# SCK_DATA_BOARD_2_0_REV_05.net
KiCad netlist of a schematic drawn in EAGLE
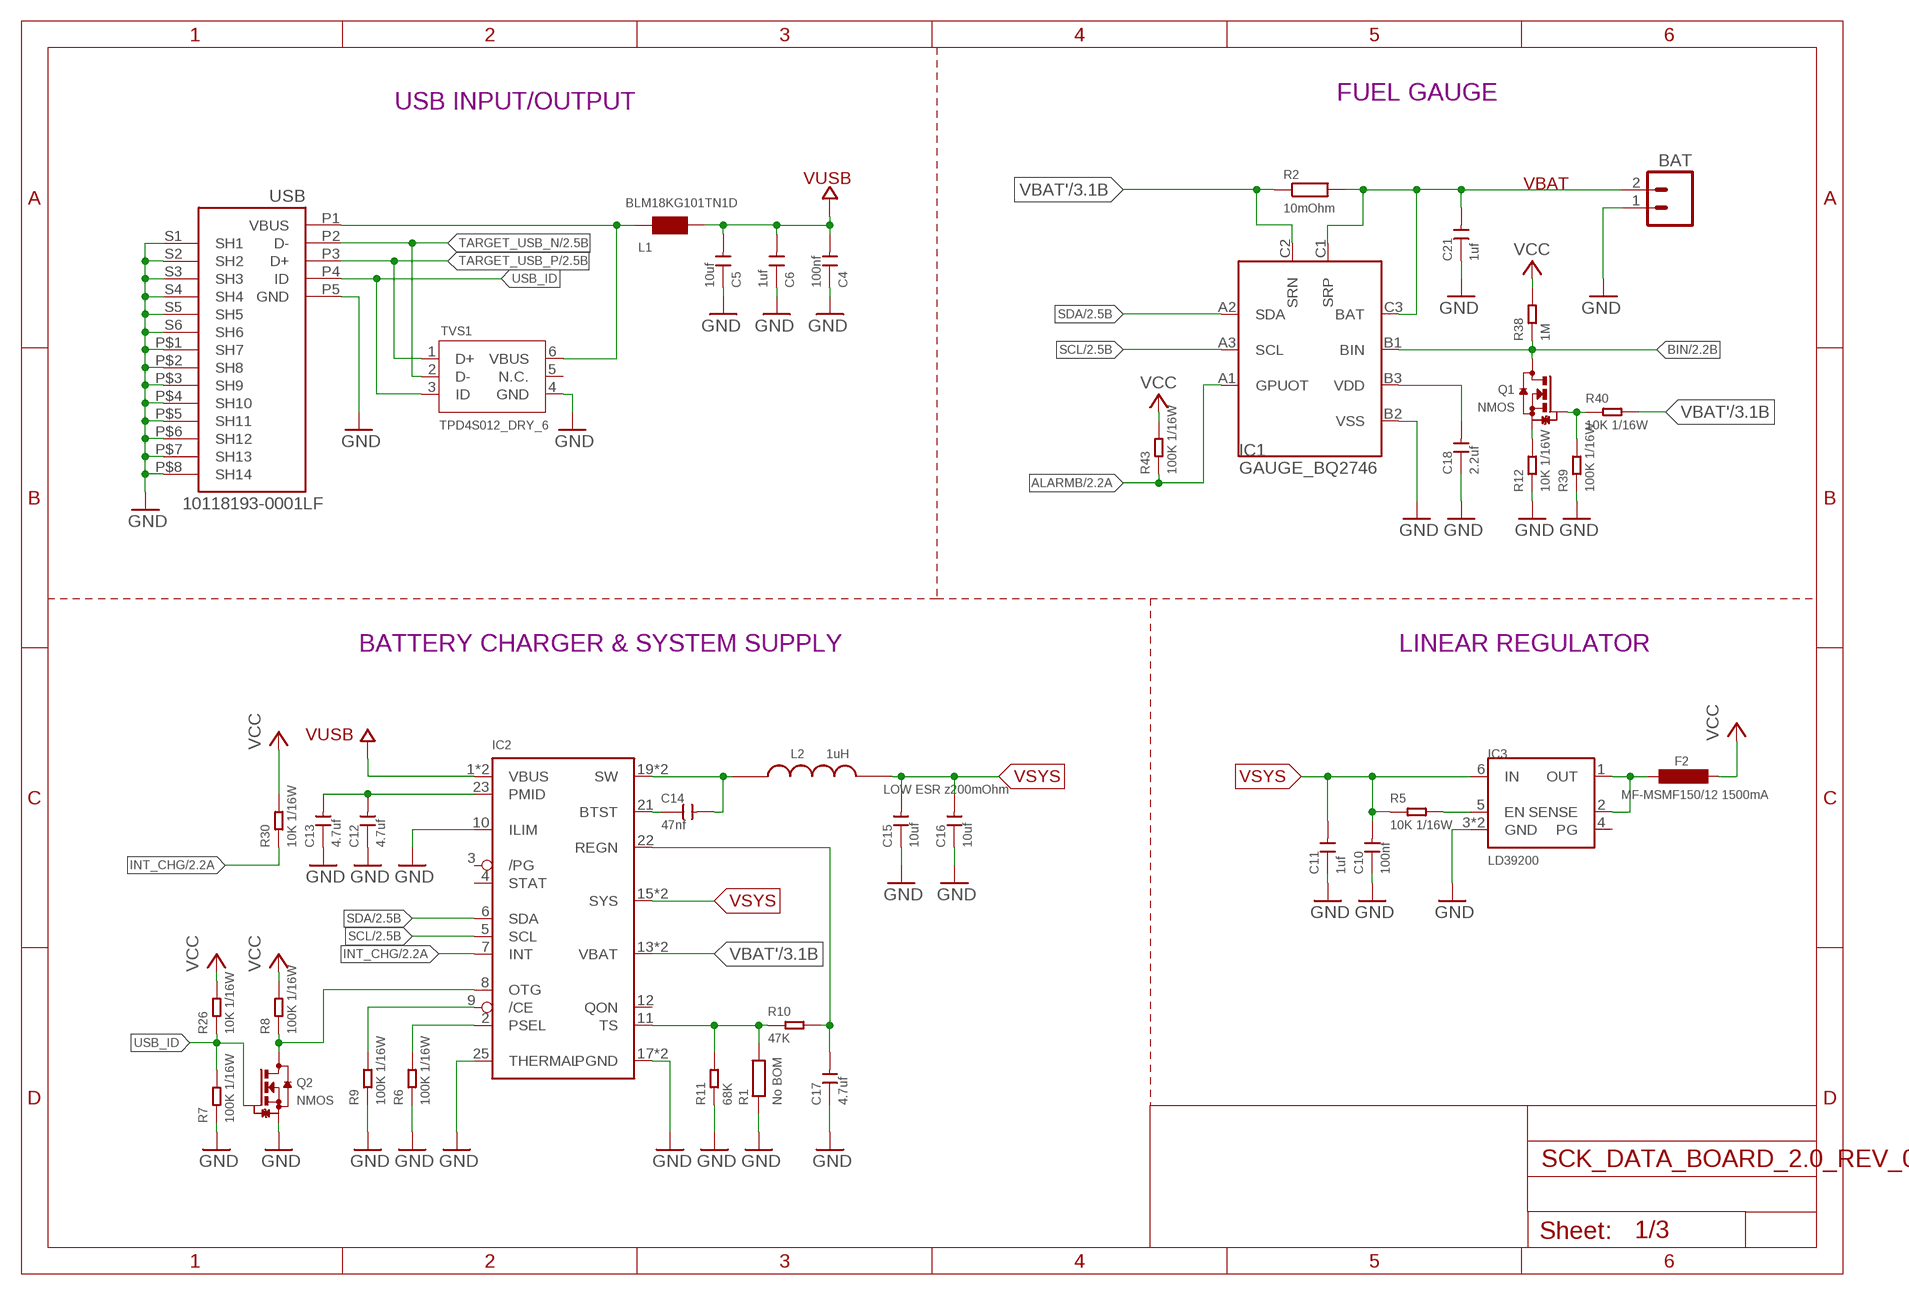
[diagram p0: schematic, sheet 1]
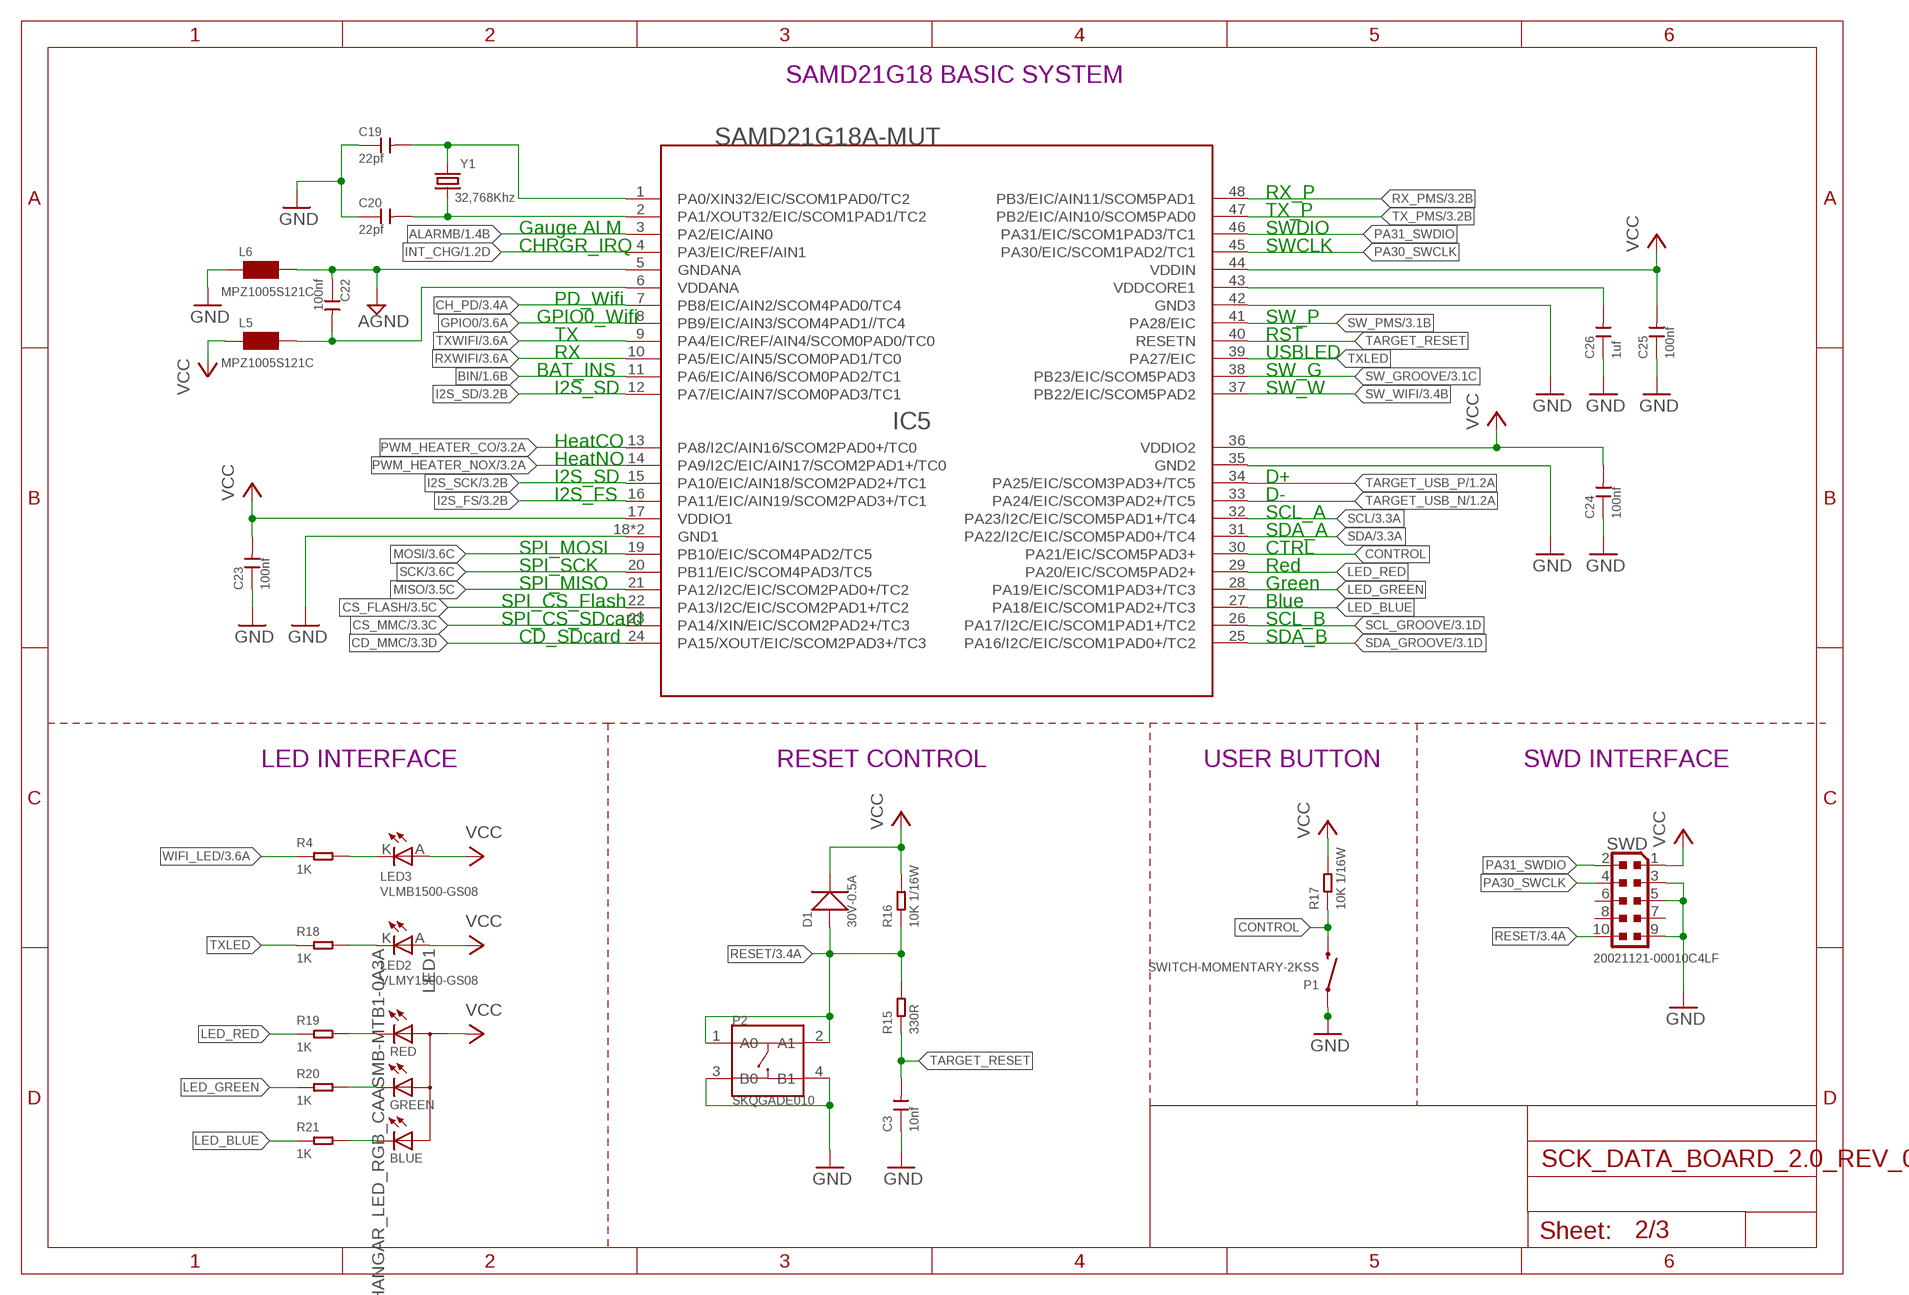
[diagram p1: schematic, sheet 2]
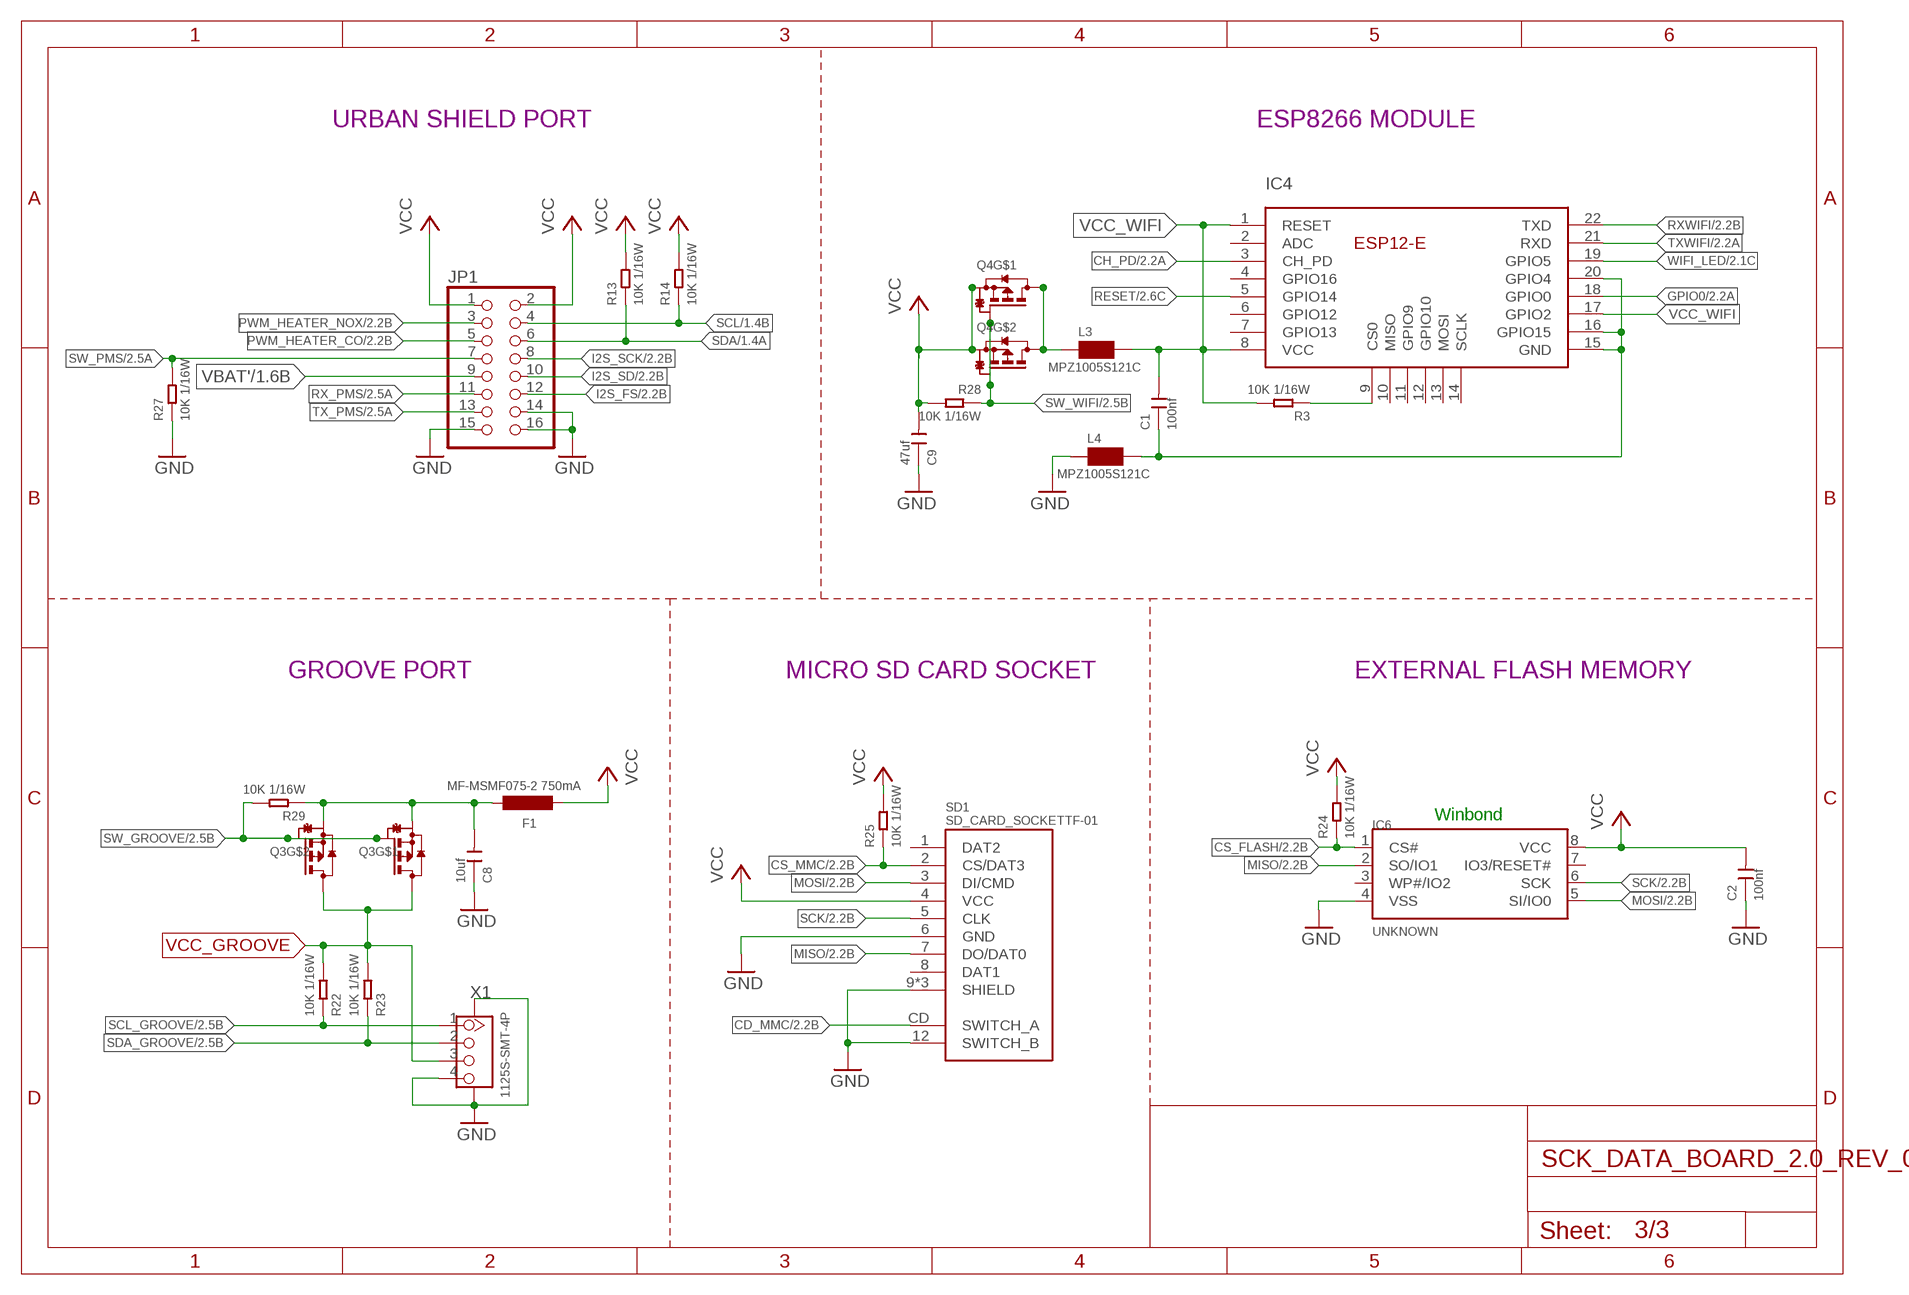
[diagram p2: schematic, sheet 3]

(export (version "E")
  (design (tool "Eeschema 10.0.6"))
  (components
    (comp (ref "BAT")
      (value "M02-JST-2MM-SMT")
      (footprint "eagle-import:S2B-PH")
      (libsource (lib "eagle-import") (part "M02-JST-2MM-SMT"))
    )
    (comp (ref "C4")
      (value "100nf")
      (footprint "eagle-import:C0805")
      (fields (field (name "MPN") "CC0805KRX7R9BB104"))
      (libsource (lib "eagle-import") (part "CERAMIC-100NF-50V-10%-X7R(0805)"))
    )
    (comp (ref "C5")
      (value "10uf")
      (footprint "eagle-import:C1206")
      (fields (field (name "MPN") "CC1206KKX5R8BB106"))
      (libsource (lib "eagle-import") (part "CERAMIC-10UF-25V-10%-X5R(1206)"))
    )
    (comp (ref "C6")
      (value "1uf")
      (footprint "eagle-import:C0805")
      (fields (field (name "MPN") "CC0805KKX7R8BB105"))
      (libsource (lib "eagle-import") (part "CERAMIC-1UF-25V-10%-X7R(0805)"))
    )
    (comp (ref "C10")
      (value "100nf")
      (footprint "eagle-import:C0603")
      (fields (field (name "MPN") "CC0603KRX7R9BB104"))
      (libsource (lib "eagle-import") (part "CERAMIC-100NF-50V-10%-X7R(0603)"))
    )
    (comp (ref "C11")
      (value "1uf")
      (footprint "eagle-import:C0805")
      (fields (field (name "MPN") "CC0805KKX7R8BB105"))
      (libsource (lib "eagle-import") (part "CERAMIC-1UF-25V-10%-X7R(0805)"))
    )
    (comp (ref "C12")
      (value "4.7uf")
      (footprint "eagle-import:C0603")
      (fields (field (name "MPN") "CC0603KRX5R6BB475"))
      (libsource (lib "eagle-import") (part "CERAMIC-4.7UF-10V-10%-X5R(0603)"))
    )
    (comp (ref "C13")
      (value "4.7uf")
      (footprint "eagle-import:C0603")
      (fields (field (name "MPN") "CC0603KRX5R6BB475"))
      (libsource (lib "eagle-import") (part "CERAMIC-4.7UF-10V-10%-X5R(0603)"))
    )
    (comp (ref "C14")
      (value "47nf")
      (footprint "eagle-import:C0402")
      (fields (field (name "MPN") "CC0402KRX7R8BB473"))
      (libsource (lib "eagle-import") (part "CERAMIC-47NF-25V-10%-X7R(0402)"))
    )
    (comp (ref "C15")
      (value "10uf")
      (footprint "eagle-import:C0603")
      (fields (field (name "MPN") "CC0603KRX5R6BB106"))
      (libsource (lib "eagle-import") (part "CERAMIC-10UF-10V-10%-X5R(0603)"))
    )
    (comp (ref "C16")
      (value "10uf")
      (footprint "eagle-import:C0603")
      (fields (field (name "MPN") "CC0603KRX5R6BB106"))
      (libsource (lib "eagle-import") (part "CERAMIC-10UF-10V-10%-X5R(0603)"))
    )
    (comp (ref "C17")
      (value "4.7uf")
      (footprint "eagle-import:C0805")
      (fields (field (name "MPN") "CC0805KKX5R8BB475"))
      (libsource (lib "eagle-import") (part "CERAMIC-4.7UF-25V-10%-X5R(0805)"))
    )
    (comp (ref "C18")
      (value "2.2uf")
      (footprint "eagle-import:C0603")
      (fields (field (name "MPN") "CC0603KRX7R6BB225"))
      (libsource (lib "eagle-import") (part "CERAMIC-2.2UF-10V-10%-X7R(0603)"))
    )
    (comp (ref "C21")
      (value "1uf")
      (footprint "eagle-import:C0805")
      (fields (field (name "MPN") "CC0805KKX7R8BB105"))
      (libsource (lib "eagle-import") (part "CERAMIC-1UF-25V-10%-X7R(0805)"))
    )
    (comp (ref "F2")
      (value "MF-MSMF150/12 1500mA")
      (footprint "eagle-import:L1812")
      (libsource (lib "eagle-import") (part "L-EUL1812"))
    )
    (comp (ref "IC1")
      (value "GAUGE_BQ2746")
      (footprint "eagle-import:BGA-9")
      (libsource (lib "eagle-import") (part "GAUGE_BQ2746"))
    )
    (comp (ref "IC2")
      (value "BQ24259_VQFN(24)")
      (footprint "eagle-import:24-PIN_VQFN_THPAD")
      (libsource (lib "eagle-import") (part "BQ24259_VQFN(24)"))
    )
    (comp (ref "IC3")
      (value "LD39200")
      (footprint "eagle-import:DFN6_3X3MM")
      (libsource (lib "eagle-import") (part "LD39200"))
    )
    (comp (ref "L1")
      (value "BLM18KG101TN1D")
      (footprint "eagle-import:WUERTH-ELEKTRONIK_0603")
      (libsource (lib "eagle-import") (part "WUERTH-ELEKTRONIK_WE-CBF_0603"))
    )
    (comp (ref "L2")
      (value "1uH")
      (footprint "eagle-import:HANGAR_C1210")
      (libsource (lib "eagle-import") (part "LQH32PN1R0NNCL"))
    )
    (comp (ref "Q1")
      (value "NMOS")
      (footprint "eagle-import:NMOS_UMT3")
      (libsource (lib "eagle-import") (part "NMOS_RJU003N03FRAT106"))
    )
    (comp (ref "Q2")
      (value "NMOS")
      (footprint "eagle-import:NMOS_UMT3")
      (libsource (lib "eagle-import") (part "NMOS_RJU003N03FRAT106"))
    )
    (comp (ref "R1")
      (value "No BOM")
      (footprint "eagle-import:HANGAR_R0402")
      (libsource (lib "eagle-import") (part "HANGAR_R-EU_R0402"))
    )
    (comp (ref "R2")
      (value "10mOhm")
      (footprint "eagle-import:HANGAR_R0603")
      (libsource (lib "eagle-import") (part "SCK_URBAN_SHIELD_v1.6_HANGAR_R-EU_R0603"))
    )
    (comp (ref "R5")
      (value "10K 1/16W")
      (footprint "eagle-import:R0402")
      (fields (field (name "MPN") "RC0402FR-0710KL"))
      (libsource (lib "eagle-import") (part "SMD-RES-10K-1%-1/16W(0402)"))
    )
    (comp (ref "R6")
      (value "100K 1/16W")
      (footprint "eagle-import:R0402")
      (fields (field (name "MPN") "RC0402JR-07100KL"))
      (libsource (lib "eagle-import") (part "SMD-RES-100K-5%-1/16W(0402)"))
    )
    (comp (ref "R7")
      (value "100K 1/16W")
      (footprint "eagle-import:R0402")
      (fields (field (name "MPN") "RC0402JR-07100KL"))
      (libsource (lib "eagle-import") (part "SMD-RES-100K-5%-1/16W(0402)"))
    )
    (comp (ref "R8")
      (value "100K 1/16W")
      (footprint "eagle-import:R0402")
      (fields (field (name "MPN") "RC0402JR-07100KL"))
      (libsource (lib "eagle-import") (part "SMD-RES-100K-5%-1/16W(0402)"))
    )
    (comp (ref "R9")
      (value "100K 1/16W")
      (footprint "eagle-import:R0402")
      (fields (field (name "MPN") "RC0402JR-07100KL"))
      (libsource (lib "eagle-import") (part "SMD-RES-100K-5%-1/16W(0402)"))
    )
    (comp (ref "R10")
      (value "47K")
      (footprint "eagle-import:R0402")
      (fields (field (name "MPN") "RC0402JR-0747KL"))
      (libsource (lib "eagle-import") (part "SMD-RES-47K-5%-1/16W(0402)"))
    )
    (comp (ref "R11")
      (value "68K")
      (footprint "eagle-import:R0402")
      (fields (field (name "MPN") "RC0402JR-0768KL"))
      (libsource (lib "eagle-import") (part "SMD-RES-68K-50V-5%(0402)"))
    )
    (comp (ref "R12")
      (value "10K 1/16W")
      (footprint "eagle-import:R0402")
      (fields (field (name "MPN") "RC0402FR-0710KL"))
      (libsource (lib "eagle-import") (part "SMD-RES-10K-1%-1/16W(0402)"))
    )
    (comp (ref "R26")
      (value "10K 1/16W")
      (footprint "eagle-import:R0402")
      (fields (field (name "MPN") "RC0402FR-0710KL"))
      (libsource (lib "eagle-import") (part "SMD-RES-10K-1%-1/16W(0402)"))
    )
    (comp (ref "R30")
      (value "10K 1/16W")
      (footprint "eagle-import:R0402")
      (fields (field (name "MPN") "RC0402FR-0710KL"))
      (libsource (lib "eagle-import") (part "SMD-RES-10K-1%-1/16W(0402)"))
    )
    (comp (ref "R38")
      (value "1M")
      (footprint "eagle-import:R0402")
      (fields (field (name "MPN") "RC0402JR-071ML"))
      (libsource (lib "eagle-import") (part "SMD-RES-1M-5%-1/16W(0402)"))
    )
    (comp (ref "R39")
      (value "100K 1/16W")
      (footprint "eagle-import:R0402")
      (fields (field (name "MPN") "RC0402JR-07100KL"))
      (libsource (lib "eagle-import") (part "Seeed-Resistor_SMD-RES-100K-5%-1/16W(0402)"))
    )
    (comp (ref "R40")
      (value "10K 1/16W")
      (footprint "eagle-import:R0402")
      (fields (field (name "MPN") "RC0402FR-0710KL"))
      (libsource (lib "eagle-import") (part "SMD-RES-10K-1%-1/16W(0402)"))
    )
    (comp (ref "R43")
      (value "100K 1/16W")
      (footprint "eagle-import:R0402")
      (fields (field (name "MPN") "RC0402JR-07100KL"))
      (libsource (lib "eagle-import") (part "Seeed-Resistor_SMD-RES-100K-5%-1/16W(0402)"))
    )
    (comp (ref "TVS1")
      (value "TPD4S012_DRY_6")
      (footprint "eagle-import:DRY6")
      (libsource (lib "eagle-import") (part "TPD4S012_DRY_6"))
    )
    (comp (ref "USB")
      (value "10118193-0001LF")
      (footprint "eagle-import:HANGAR_CON2_USB_MICRO_B_AT")
      (libsource (lib "eagle-import") (part "HANGAR_MYCON2_USB-MINI-B"))
    )
    (comp (ref "C3")
      (value "10nf")
      (footprint "eagle-import:C0402")
      (fields (field (name "MPN") "CC0402KRX7R9BB103"))
      (libsource (lib "eagle-import") (part "CERAMIC-10NF-50V-10%-X7R(0402)"))
    )
    (comp (ref "C19")
      (value "22pf")
      (footprint "eagle-import:C0402")
      (fields (field (name "MPN") "CC0402JRNPO9BN220"))
      (libsource (lib "eagle-import") (part "CERAMIC-22PF-50V-5%-NPO(0402)"))
    )
    (comp (ref "C20")
      (value "22pf")
      (footprint "eagle-import:C0402")
      (fields (field (name "MPN") "CC0402JRNPO9BN220"))
      (libsource (lib "eagle-import") (part "CERAMIC-22PF-50V-5%-NPO(0402)"))
    )
    (comp (ref "C22")
      (value "100nf")
      (footprint "eagle-import:C0402")
      (fields (field (name "MPN") "CC0402KRX7R8BB104"))
      (libsource (lib "eagle-import") (part "CERAMIC-100NF-25V-10%-X7R(0402)"))
    )
    (comp (ref "C23")
      (value "100nf")
      (footprint "eagle-import:C0402")
      (fields (field (name "MPN") "CC0402KRX7R8BB104"))
      (libsource (lib "eagle-import") (part "CERAMIC-100NF-25V-10%-X7R(0402)"))
    )
    (comp (ref "C24")
      (value "100nf")
      (footprint "eagle-import:C0402")
      (fields (field (name "MPN") "CC0402KRX7R8BB104"))
      (libsource (lib "eagle-import") (part "CERAMIC-100NF-25V-10%-X7R(0402)"))
    )
    (comp (ref "C25")
      (value "100nf")
      (footprint "eagle-import:C0402")
      (fields (field (name "MPN") "CC0402KRX7R8BB104"))
      (libsource (lib "eagle-import") (part "CERAMIC-100NF-25V-10%-X7R(0402)"))
    )
    (comp (ref "C26")
      (value "1uf")
      (footprint "eagle-import:C0402")
      (fields (field (name "MPN") "CC0402KRX5R6BB105"))
      (libsource (lib "eagle-import") (part "CERAMIC-1UF-10V-10%-X5R(0402)"))
    )
    (comp (ref "D1")
      (value "30V-0.5A")
      (footprint "eagle-import:SOD-323")
      (fields (field (name "MPN") "LRB551V-30T1G"))
      (libsource (lib "eagle-import") (part "SMD-DIODE-SCHOTTKY-30V-0.5A(SOD-323)"))
    )
    (comp (ref "IC5")
      (value "SAMD21G18A-MUT")
      (footprint "eagle-import:HANGAR_QFN48-7X7")
      (libsource (lib "eagle-import") (part "HANGAR_SAMD21G18A-MUT"))
    )
    (comp (ref "L5")
      (value "MPZ1005S121C")
      (footprint "eagle-import:0402")
      (libsource (lib "eagle-import") (part "WE-CBF_0402"))
    )
    (comp (ref "L6")
      (value "MPZ1005S121C")
      (footprint "eagle-import:0402")
      (libsource (lib "eagle-import") (part "WE-CBF_0402"))
    )
    (comp (ref "LED1")
      (value "HANGAR_LED_RGB_CAASMB-MTB1-0A3A")
      (footprint "eagle-import:HANGAR_P-LCC-4")
      (libsource (lib "eagle-import") (part "HANGAR_LED_RGB_CAASMB-MTB1-0A3A"))
    )
    (comp (ref "LED2")
      (value "VLMY1500-GS08")
      (footprint "eagle-import:DIODE_0402_R")
      (libsource (lib "eagle-import") (part "LED_SMALL"))
    )
    (comp (ref "LED3")
      (value "VLMB1500-GS08")
      (footprint "eagle-import:DIODE_0402_R")
      (libsource (lib "eagle-import") (part "LED_SMALL"))
    )
    (comp (ref "P1")
      (value "SWITCH-MOMENTARY-2KSS")
      (footprint "eagle-import:KSS241G")
      (libsource (lib "eagle-import") (part "SWITCH-MOMENTARY-2KSS"))
    )
    (comp (ref "P2")
      (value "SKQGADE010")
      (footprint "eagle-import:SW4-SMD-5.2X5.2X1.5MM")
      (libsource (lib "eagle-import") (part "SMD-BUTTON(4P-5.2X5.2X1.5MM-SKQGADE010)-SKQGADE010"))
    )
    (comp (ref "R4")
      (value "1K")
      (footprint "eagle-import:R0402")
      (fields (field (name "MPN") "RC0402JR-071KL"))
      (libsource (lib "eagle-import") (part "SMD-RES-1K-5%-1/16W(0402)"))
    )
    (comp (ref "R15")
      (value "330R")
      (footprint "eagle-import:R0402")
      (fields (field (name "MPN") "RC0402FR-07330RL"))
      (libsource (lib "eagle-import") (part "SMD-RES-330R-1%-1/16W(0402)"))
    )
    (comp (ref "R16")
      (value "10K 1/16W")
      (footprint "eagle-import:R0402")
      (fields (field (name "MPN") "RC0402FR-0710KL"))
      (libsource (lib "eagle-import") (part "SMD-RES-10K-1%-1/16W(0402)"))
    )
    (comp (ref "R17")
      (value "10K 1/16W")
      (footprint "eagle-import:R0402")
      (fields (field (name "MPN") "RC0402FR-0710KL"))
      (libsource (lib "eagle-import") (part "SMD-RES-10K-1%-1/16W(0402)"))
    )
    (comp (ref "R18")
      (value "1K")
      (footprint "eagle-import:R0402")
      (fields (field (name "MPN") "RC0402JR-071KL"))
      (libsource (lib "eagle-import") (part "SMD-RES-1K-5%-1/16W(0402)"))
    )
    (comp (ref "R19")
      (value "1K")
      (footprint "eagle-import:R0402")
      (fields (field (name "MPN") "RC0402JR-071KL"))
      (libsource (lib "eagle-import") (part "SMD-RES-1K-5%-1/16W(0402)"))
    )
    (comp (ref "R20")
      (value "1K")
      (footprint "eagle-import:R0402")
      (fields (field (name "MPN") "RC0402JR-071KL"))
      (libsource (lib "eagle-import") (part "SMD-RES-1K-5%-1/16W(0402)"))
    )
    (comp (ref "R21")
      (value "1K")
      (footprint "eagle-import:R0402")
      (fields (field (name "MPN") "RC0402JR-071KL"))
      (libsource (lib "eagle-import") (part "SMD-RES-1K-5%-1/16W(0402)"))
    )
    (comp (ref "SWD")
      (value "20021121-00010C4LF")
      (footprint "eagle-import:2X05_SMD_1.27MM")
      (libsource (lib "eagle-import") (part "PINHEAD_PINHD-2X5SMD"))
    )
    (comp (ref "Y1")
      (value "32,768Khz")
      (footprint "eagle-import:RESONATOR_EPSON_FC_145")
      (fields (field (name "PART_NUMBER") "ABS07-32.768KHZ-T"))
      (libsource (lib "eagle-import") (part "0213_ABS07-32.768KHZ-T"))
    )
    (comp (ref "C1")
      (value "100nf")
      (footprint "eagle-import:C0402")
      (fields (field (name "MPN") "CC0402KRX7R8BB104"))
      (libsource (lib "eagle-import") (part "CERAMIC-100NF-25V-10%-X7R(0402)"))
    )
    (comp (ref "C2")
      (value "100nf")
      (footprint "eagle-import:C0402")
      (fields (field (name "MPN") "CC0402KRX7R8BB104"))
      (libsource (lib "eagle-import") (part "CERAMIC-100NF-25V-10%-X7R(0402)"))
    )
    (comp (ref "C8")
      (value "10uf")
      (footprint "eagle-import:C1206")
      (fields (field (name "MPN") "CC1206KKX5R8BB106"))
      (libsource (lib "eagle-import") (part "CERAMIC-10UF-25V-10%-X5R(1206)"))
    )
    (comp (ref "C9")
      (value "47uf")
      (footprint "eagle-import:C1210")
      (fields (field (name "MPN") "GRM32ER71A476ME15L"))
      (libsource (lib "eagle-import") (part "CERAMIC-47UF-10V-20%-X7R(1210)"))
    )
    (comp (ref "F1")
      (value "MF-MSMF075-2 750mA")
      (footprint "eagle-import:L1812")
      (libsource (lib "eagle-import") (part "L-EUL1812"))
    )
    (comp (ref "IC4")
      (value "HANGAR_ESP-12-E")
      (footprint "eagle-import:HANGAR_ESP12-E")
      (libsource (lib "eagle-import") (part "HANGAR_ESP-12-E"))
    )
    (comp (ref "IC6")
      (value "UNKNOWN")
      (footprint "eagle-import:SOIC_8-208MILS")
      (libsource (lib "eagle-import") (part "FLASH_S25FL064L"))
    )
    (comp (ref "JP1")
      (value "PINHD_2X8FEM_SMD")
      (footprint "eagle-import:PINHD_2X8_SMD_FEMALE_UNHOLED")
      (libsource (lib "eagle-import") (part "PINHD_2X8FEM_SMD"))
    )
    (comp (ref "L3")
      (value "MPZ1005S121C")
      (footprint "eagle-import:0402")
      (libsource (lib "eagle-import") (part "WE-CBF_0402"))
    )
    (comp (ref "L4")
      (value "MPZ1005S121C")
      (footprint "eagle-import:0402")
      (libsource (lib "eagle-import") (part "WE-CBF_0402"))
    )
    (comp (ref "Q3")
      (value "PMOS")
      (footprint "eagle-import:HANGAR_POWERPAKSC70-6L")
      (libsource (lib "eagle-import") (part "MOSFETP_BOTH"))
    )
    (comp (ref "Q4")
      (value "PMOS")
      (footprint "eagle-import:HANGAR_POWERPAKSC70-6L")
      (libsource (lib "eagle-import") (part "MOSFETP_BOTH"))
    )
    (comp (ref "R3")
      (value "10K 1/16W")
      (footprint "eagle-import:R0402")
      (fields (field (name "MPN") "RC0402FR-0710KL"))
      (libsource (lib "eagle-import") (part "SMD-RES-10K-1%-1/16W(0402)"))
    )
    (comp (ref "R13")
      (value "10K 1/16W")
      (footprint "eagle-import:R0402")
      (fields (field (name "MPN") "RC0402FR-0710KL"))
      (libsource (lib "eagle-import") (part "SMD-RES-10K-1%-1/16W(0402)"))
    )
    (comp (ref "R14")
      (value "10K 1/16W")
      (footprint "eagle-import:R0402")
      (fields (field (name "MPN") "RC0402FR-0710KL"))
      (libsource (lib "eagle-import") (part "SMD-RES-10K-1%-1/16W(0402)"))
    )
    (comp (ref "R22")
      (value "10K 1/16W")
      (footprint "eagle-import:R0402")
      (fields (field (name "MPN") "RC0402FR-0710KL"))
      (libsource (lib "eagle-import") (part "SMD-RES-10K-1%-1/16W(0402)"))
    )
    (comp (ref "R23")
      (value "10K 1/16W")
      (footprint "eagle-import:R0402")
      (fields (field (name "MPN") "RC0402FR-0710KL"))
      (libsource (lib "eagle-import") (part "SMD-RES-10K-1%-1/16W(0402)"))
    )
    (comp (ref "R24")
      (value "10K 1/16W")
      (footprint "eagle-import:R0402")
      (fields (field (name "MPN") "RC0402FR-0710KL"))
      (libsource (lib "eagle-import") (part "SMD-RES-10K-1%-1/16W(0402)"))
    )
    (comp (ref "R25")
      (value "10K 1/16W")
      (footprint "eagle-import:R0402")
      (fields (field (name "MPN") "RC0402FR-0710KL"))
      (libsource (lib "eagle-import") (part "SMD-RES-10K-1%-1/16W(0402)"))
    )
    (comp (ref "R27")
      (value "10K 1/16W")
      (footprint "eagle-import:R0402")
      (fields (field (name "MPN") "RC0402FR-0710KL"))
      (libsource (lib "eagle-import") (part "Seeed-Resistor_SMD-RES-10K-1%-1/16W(0402)"))
    )
    (comp (ref "R28")
      (value "10K 1/16W")
      (footprint "eagle-import:R0402")
      (fields (field (name "MPN") "RC0402FR-0710KL"))
      (libsource (lib "eagle-import") (part "Seeed-Resistor_SMD-RES-10K-1%-1/16W(0402)"))
    )
    (comp (ref "R29")
      (value "10K 1/16W")
      (footprint "eagle-import:R0402")
      (fields (field (name "MPN") "RC0402FR-0710KL"))
      (libsource (lib "eagle-import") (part "Seeed-Resistor_SMD-RES-10K-1%-1/16W(0402)"))
    )
    (comp (ref "SD1")
      (value "SD_CARD_SOCKETTF-01")
      (footprint "eagle-import:TF-01")
      (libsource (lib "eagle-import") (part "SD_CARD_SOCKETTF-01"))
    )
    (comp (ref "X1")
      (value "1125S-SMT-4P")
      (footprint "eagle-import:HW4-SMD-2.0")
      (libsource (lib "eagle-import") (part "GROVE-CONNECTOR-SMD'DD'"))
    )
  )
  (nets
    (net (code "1") (name "AGND") (class "Default")
      (node (ref "C22") (pin "1") (pinfunction "1_1") (pintype "passive"))
      (node (ref "IC5") (pin "5") (pinfunction "GNDANA_5") (pintype "power_in"))
      (node (ref "L6") (pin "2") (pinfunction "2_2") (pintype "passive"))
    )
    (net (code "2") (name "ALARMB") (class "Default")
      (node (ref "IC1") (pin "A1") (pinfunction "GPUOT_A1") (pintype "bidirectional"))
      (node (ref "IC5") (pin "3") (pinfunction "PA2/EIC/AIN0_3") (pintype "bidirectional"))
      (node (ref "R43") (pin "1") (pinfunction "1_1") (pintype "passive"))
    )
    (net (code "3") (name "BIN") (class "Default")
      (node (ref "IC1") (pin "B1") (pinfunction "BIN_B1") (pintype "bidirectional"))
      (node (ref "IC5") (pin "11") (pinfunction "PA6/EIC/AIN6/SCOM0PAD2/TC1_11") (pintype "bidirectional"))
      (node (ref "Q1") (pin "3") (pinfunction "D_3") (pintype "passive"))
      (node (ref "R38") (pin "1") (pinfunction "1_1") (pintype "passive"))
    )
    (net (code "4") (name "CD_MMC") (class "Default")
      (node (ref "IC5") (pin "24") (pinfunction "PA15/XOUT/EIC/SCOM2PAD3+/TC3_24") (pintype "bidirectional"))
      (node (ref "SD1") (pin "CD") (pinfunction "SWITCH_A_CD") (pintype "bidirectional"))
    )
    (net (code "5") (name "CH_PD") (class "Default")
      (node (ref "IC4") (pin "3") (pinfunction "CH_PD_3") (pintype "input"))
      (node (ref "IC5") (pin "7") (pinfunction "PB8/EIC/AIN2/SCOM4PAD0/TC4_7") (pintype "bidirectional"))
    )
    (net (code "6") (name "CONTROL") (class "Default")
      (node (ref "IC5") (pin "30") (pinfunction "PA21/EIC/SCOM5PAD3+_30") (pintype "bidirectional"))
      (node (ref "P1") (pin "2") (pinfunction "2_2") (pintype "passive"))
      (node (ref "R17") (pin "1") (pinfunction "1_1") (pintype "passive"))
    )
    (net (code "7") (name "CS_FLASH") (class "Default")
      (node (ref "IC5") (pin "22") (pinfunction "PA13/I2C/EIC/SCOM2PAD1+/TC2_22") (pintype "bidirectional"))
      (node (ref "IC6") (pin "1") (pinfunction "CS#_1") (pintype "bidirectional"))
      (node (ref "R24") (pin "1") (pinfunction "1_1") (pintype "passive"))
    )
    (net (code "8") (name "CS_MMC") (class "Default")
      (node (ref "IC5") (pin "23") (pinfunction "PA14/XIN/EIC/SCOM2PAD2+/TC3_23") (pintype "bidirectional"))
      (node (ref "R25") (pin "1") (pinfunction "1_1") (pintype "passive"))
      (node (ref "SD1") (pin "2") (pinfunction "CS/DAT3_2") (pintype "bidirectional"))
    )
    (net (code "9") (name "GND") (class "Default")
      (node (ref "BAT") (pin "1") (pinfunction "1_1") (pintype "passive"))
      (node (ref "C10") (pin "1") (pinfunction "1_1") (pintype "passive"))
      (node (ref "C11") (pin "1") (pinfunction "1_1") (pintype "passive"))
      (node (ref "C12") (pin "1") (pinfunction "1_1") (pintype "passive"))
      (node (ref "C13") (pin "1") (pinfunction "1_1") (pintype "passive"))
      (node (ref "C15") (pin "1") (pinfunction "1_1") (pintype "passive"))
      (node (ref "C16") (pin "1") (pinfunction "1_1") (pintype "passive"))
      (node (ref "C17") (pin "1") (pinfunction "1_1") (pintype "passive"))
      (node (ref "C18") (pin "1") (pinfunction "1_1") (pintype "passive"))
      (node (ref "C19") (pin "1") (pinfunction "1_1") (pintype "passive"))
      (node (ref "C2") (pin "1") (pinfunction "1_1") (pintype "passive"))
      (node (ref "C20") (pin "1") (pinfunction "1_1") (pintype "passive"))
      (node (ref "C21") (pin "1") (pinfunction "1_1") (pintype "passive"))
      (node (ref "C23") (pin "1") (pinfunction "1_1") (pintype "passive"))
      (node (ref "C24") (pin "1") (pinfunction "1_1") (pintype "passive"))
      (node (ref "C25") (pin "1") (pinfunction "1_1") (pintype "passive"))
      (node (ref "C26") (pin "1") (pinfunction "1_1") (pintype "passive"))
      (node (ref "C3") (pin "1") (pinfunction "1_1") (pintype "passive"))
      (node (ref "C4") (pin "1") (pinfunction "1_1") (pintype "passive"))
      (node (ref "C5") (pin "1") (pinfunction "1_1") (pintype "passive"))
      (node (ref "C6") (pin "1") (pinfunction "1_1") (pintype "passive"))
      (node (ref "C8") (pin "1") (pinfunction "1_1") (pintype "passive"))
      (node (ref "C9") (pin "1") (pinfunction "1_1") (pintype "passive"))
      (node (ref "IC1") (pin "B2") (pinfunction "VSS_B2") (pintype "bidirectional"))
      (node (ref "IC2") (pin "10") (pinfunction "ILIM_10") (pintype "bidirectional"))
      (node (ref "IC2") (pin "17") (pinfunction "PGND_17") (pintype "bidirectional"))
      (node (ref "IC2") (pin "18") (pinfunction "PGND_18") (pintype "bidirectional"))
      (node (ref "IC2") (pin "25") (pinfunction "THERMAL_25") (pintype "bidirectional"))
      (node (ref "IC3") (pin "3") (pinfunction "GND_3") (pintype "bidirectional"))
      (node (ref "IC3") (pin "7") (pinfunction "GND_7") (pintype "bidirectional"))
      (node (ref "IC5") (pin "18") (pinfunction "GND1_18") (pintype "power_in"))
      (node (ref "IC5") (pin "35") (pinfunction "GND2_35") (pintype "power_in"))
      (node (ref "IC5") (pin "42") (pinfunction "GND3_42") (pintype "power_in"))
      (node (ref "IC5") (pin "TP") (pinfunction "GND1_TP") (pintype "power_in"))
      (node (ref "IC6") (pin "4") (pinfunction "VSS_4") (pintype "bidirectional"))
      (node (ref "JP1") (pin "14") (pinfunction "14_14") (pintype "passive"))
      (node (ref "JP1") (pin "15") (pinfunction "15_15") (pintype "passive"))
      (node (ref "JP1") (pin "16") (pinfunction "16_16") (pintype "passive"))
      (node (ref "L4") (pin "2") (pinfunction "2_2") (pintype "passive"))
      (node (ref "L6") (pin "1") (pinfunction "1_1") (pintype "passive"))
      (node (ref "P1") (pin "1") (pinfunction "1_1") (pintype "passive"))
      (node (ref "P2") (pin "3") (pinfunction "B0_3") (pintype "bidirectional"))
      (node (ref "P2") (pin "4") (pinfunction "B1_4") (pintype "bidirectional"))
      (node (ref "Q2") (pin "1") (pinfunction "S_1") (pintype "passive"))
      (node (ref "R1") (pin "1") (pinfunction "1_1") (pintype "passive"))
      (node (ref "R11") (pin "1") (pinfunction "1_1") (pintype "passive"))
      (node (ref "R12") (pin "1") (pinfunction "1_1") (pintype "passive"))
      (node (ref "R27") (pin "1") (pinfunction "1_1") (pintype "passive"))
      (node (ref "R39") (pin "1") (pinfunction "1_1") (pintype "passive"))
      (node (ref "R6") (pin "1") (pinfunction "1_1") (pintype "passive"))
      (node (ref "R7") (pin "1") (pinfunction "1_1") (pintype "passive"))
      (node (ref "R9") (pin "1") (pinfunction "1_1") (pintype "passive"))
      (node (ref "SD1") (pin "10") (pinfunction "SHIELD_10") (pintype "bidirectional"))
      (node (ref "SD1") (pin "11") (pinfunction "SHIELD_11") (pintype "bidirectional"))
      (node (ref "SD1") (pin "12") (pinfunction "SWITCH_B_12") (pintype "bidirectional"))
      (node (ref "SD1") (pin "6") (pinfunction "GND_6") (pintype "bidirectional"))
      (node (ref "SD1") (pin "9") (pinfunction "SHIELD_9") (pintype "bidirectional"))
      (node (ref "SWD") (pin "3") (pinfunction "3_3") (pintype "passive"))
      (node (ref "SWD") (pin "5") (pinfunction "5_5") (pintype "passive"))
      (node (ref "SWD") (pin "9") (pinfunction "9_9") (pintype "passive"))
      (node (ref "TVS1") (pin "4") (pinfunction "GND_4") (pintype "passive"))
      (node (ref "USB") (pin "P$1") (pinfunction "SH7_P$1") (pintype "passive"))
      (node (ref "USB") (pin "P$2") (pinfunction "SH8_P$2") (pintype "passive"))
      (node (ref "USB") (pin "P$3") (pinfunction "SH9_P$3") (pintype "passive"))
      (node (ref "USB") (pin "P$4") (pinfunction "SH10_P$4") (pintype "passive"))
      (node (ref "USB") (pin "P$5") (pinfunction "SH11_P$5") (pintype "passive"))
      (node (ref "USB") (pin "P$6") (pinfunction "SH12_P$6") (pintype "passive"))
      (node (ref "USB") (pin "P$7") (pinfunction "SH13_P$7") (pintype "passive"))
      (node (ref "USB") (pin "P$8") (pinfunction "SH14_P$8") (pintype "passive"))
      (node (ref "USB") (pin "P5") (pinfunction "GND_P5") (pintype "passive"))
      (node (ref "USB") (pin "S1") (pinfunction "SH1_S1") (pintype "passive"))
      (node (ref "USB") (pin "S2") (pinfunction "SH2_S2") (pintype "passive"))
      (node (ref "USB") (pin "S3") (pinfunction "SH3_S3") (pintype "passive"))
      (node (ref "USB") (pin "S4") (pinfunction "SH4_S4") (pintype "passive"))
      (node (ref "USB") (pin "S5") (pinfunction "SH5_S5") (pintype "passive"))
      (node (ref "USB") (pin "S6") (pinfunction "SH6_S6") (pintype "passive"))
      (node (ref "X1") (pin "4") (pinfunction "4_4") (pintype "bidirectional"))
      (node (ref "X1") (pin "SS1") (pinfunction "SS1_SS1") (pintype "bidirectional"))
      (node (ref "X1") (pin "SS2") (pinfunction "SS2_SS2") (pintype "bidirectional"))
    )
    (net (code "10") (name "GPIO0") (class "Default")
      (node (ref "IC4") (pin "18") (pinfunction "GPIO0_18") (pintype "bidirectional"))
      (node (ref "IC5") (pin "8") (pinfunction "PB9/EIC/AIN3/SCOM4PAD1//TC4_8") (pintype "bidirectional"))
    )
    (net (code "11") (name "I2S_FS") (class "Default")
      (node (ref "IC5") (pin "16") (pinfunction "PA11/EIC/AIN19/SCOM2PAD3+/TC1_16") (pintype "bidirectional"))
      (node (ref "JP1") (pin "12") (pinfunction "12_12") (pintype "passive"))
    )
    (net (code "12") (name "I2S_SCK") (class "Default")
      (node (ref "IC5") (pin "15") (pinfunction "PA10/EIC/AIN18/SCOM2PAD2+/TC1_15") (pintype "bidirectional"))
      (node (ref "JP1") (pin "8") (pinfunction "8_8") (pintype "passive"))
    )
    (net (code "13") (name "I2S_SD") (class "Default")
      (node (ref "IC5") (pin "12") (pinfunction "PA7/EIC/AIN7/SCOM0PAD3/TC1_12") (pintype "bidirectional"))
      (node (ref "JP1") (pin "10") (pinfunction "10_10") (pintype "passive"))
    )
    (net (code "14") (name "INT_CHG") (class "Default")
      (node (ref "IC2") (pin "7") (pinfunction "INT_7") (pintype "bidirectional"))
      (node (ref "IC5") (pin "4") (pinfunction "PA3/EIC/REF/AIN1_4") (pintype "bidirectional"))
      (node (ref "R30") (pin "1") (pinfunction "1_1") (pintype "passive"))
    )
    (net (code "15") (name "LED_BLUE") (class "Default")
      (node (ref "IC5") (pin "27") (pinfunction "PA18/EIC/SCOM1PAD2+/TC3_27") (pintype "bidirectional"))
      (node (ref "R21") (pin "1") (pinfunction "1_1") (pintype "passive"))
    )
    (net (code "16") (name "LED_GREEN") (class "Default")
      (node (ref "IC5") (pin "28") (pinfunction "PA19/EIC/SCOM1PAD3+/TC3_28") (pintype "bidirectional"))
      (node (ref "R20") (pin "1") (pinfunction "1_1") (pintype "passive"))
    )
    (net (code "17") (name "LED_RED") (class "Default")
      (node (ref "IC5") (pin "29") (pinfunction "PA20/EIC/SCOM5PAD2+_29") (pintype "bidirectional"))
      (node (ref "R19") (pin "1") (pinfunction "1_1") (pintype "passive"))
    )
    (net (code "18") (name "MISO") (class "Default")
      (node (ref "IC5") (pin "21") (pinfunction "PA12/I2C/EIC/SCOM2PAD0+/TC2_21") (pintype "bidirectional"))
      (node (ref "IC6") (pin "2") (pinfunction "SO/IO1_2") (pintype "bidirectional"))
      (node (ref "SD1") (pin "7") (pinfunction "DO/DAT0_7") (pintype "bidirectional"))
    )
    (net (code "19") (name "MOSI") (class "Default")
      (node (ref "IC5") (pin "19") (pinfunction "PB10/EIC/SCOM4PAD2/TC5_19") (pintype "bidirectional"))
      (node (ref "IC6") (pin "5") (pinfunction "SI/IO0_5") (pintype "bidirectional"))
      (node (ref "SD1") (pin "3") (pinfunction "DI/CMD_3") (pintype "bidirectional"))
    )
    (net (code "20") (name "Net-(C14-Pad2)") (class "Default")
      (node (ref "C14") (pin "2") (pinfunction "2_2") (pintype "passive"))
      (node (ref "IC2") (pin "19") (pinfunction "SW_19") (pintype "bidirectional"))
      (node (ref "IC2") (pin "20") (pinfunction "SW_20") (pintype "bidirectional"))
      (node (ref "L2") (pin "1") (pinfunction "1_1") (pintype "bidirectional"))
    )
    (net (code "21") (name "Net-(IC1-VDD)") (class "Default")
      (node (ref "C18") (pin "2") (pinfunction "2_2") (pintype "passive"))
      (node (ref "IC1") (pin "B3") (pinfunction "VDD_B3") (pintype "bidirectional"))
    )
    (net (code "22") (name "Net-(IC2-BTST)") (class "Default")
      (node (ref "C14") (pin "1") (pinfunction "1_1") (pintype "passive"))
      (node (ref "IC2") (pin "21") (pinfunction "BTST_21") (pintype "bidirectional"))
    )
    (net (code "23") (name "Net-(IC2-OTG)") (class "Default")
      (node (ref "IC2") (pin "8") (pinfunction "OTG_8") (pintype "bidirectional"))
      (node (ref "Q2") (pin "3") (pinfunction "D_3") (pintype "passive"))
      (node (ref "R8") (pin "1") (pinfunction "1_1") (pintype "passive"))
    )
    (net (code "24") (name "Net-(IC2-PMID)") (class "Default")
      (node (ref "C12") (pin "2") (pinfunction "2_2") (pintype "passive"))
      (node (ref "C13") (pin "2") (pinfunction "2_2") (pintype "passive"))
      (node (ref "IC2") (pin "23") (pinfunction "PMID_23") (pintype "bidirectional"))
    )
    (net (code "25") (name "Net-(IC2-PSEL)") (class "Default")
      (node (ref "IC2") (pin "2") (pinfunction "PSEL_2") (pintype "bidirectional"))
      (node (ref "R6") (pin "2") (pinfunction "2_2") (pintype "passive"))
    )
    (net (code "26") (name "Net-(IC2-REGN)") (class "Default")
      (node (ref "C17") (pin "2") (pinfunction "2_2") (pintype "passive"))
      (node (ref "IC2") (pin "22") (pinfunction "REGN_22") (pintype "bidirectional"))
      (node (ref "R10") (pin "2") (pinfunction "2_2") (pintype "passive"))
    )
    (net (code "27") (name "Net-(IC2-TS)") (class "Default")
      (node (ref "IC2") (pin "11") (pinfunction "TS_11") (pintype "bidirectional"))
      (node (ref "R1") (pin "2") (pinfunction "2_2") (pintype "passive"))
      (node (ref "R10") (pin "1") (pinfunction "1_1") (pintype "passive"))
      (node (ref "R11") (pin "2") (pinfunction "2_2") (pintype "passive"))
    )
    (net (code "28") (name "Net-(IC2-{slash}CE)") (class "Default")
      (node (ref "IC2") (pin "9") (pinfunction "/CE_9") (pintype "bidirectional"))
      (node (ref "R9") (pin "2") (pinfunction "2_2") (pintype "passive"))
    )
    (net (code "29") (name "Net-(IC3-EN)") (class "Default")
      (node (ref "IC3") (pin "5") (pinfunction "EN_5") (pintype "bidirectional"))
      (node (ref "R5") (pin "2") (pinfunction "2_2") (pintype "passive"))
    )
    (net (code "30") (name "Net-(IC3-OUT)") (class "Default")
      (node (ref "F2") (pin "2") (pinfunction "2_2") (pintype "passive"))
      (node (ref "IC3") (pin "1") (pinfunction "OUT_1") (pintype "bidirectional"))
      (node (ref "IC3") (pin "2") (pinfunction "SENSE_2") (pintype "bidirectional"))
    )
    (net (code "31") (name "Net-(IC4-CS0)") (class "Default")
      (node (ref "IC4") (pin "9") (pinfunction "CS0_9") (pintype "input"))
      (node (ref "R3") (pin "1") (pinfunction "1_1") (pintype "passive"))
    )
    (net (code "32") (name "Net-(IC4-GND)") (class "Default")
      (node (ref "C1") (pin "1") (pinfunction "1_1") (pintype "passive"))
      (node (ref "IC4") (pin "15") (pinfunction "GND_15") (pintype "power_in"))
      (node (ref "IC4") (pin "16") (pinfunction "GPIO15_16") (pintype "bidirectional"))
      (node (ref "IC4") (pin "20") (pinfunction "GPIO4_20") (pintype "bidirectional"))
      (node (ref "L4") (pin "1") (pinfunction "1_1") (pintype "passive"))
    )
    (net (code "33") (name "Net-(IC5-PA0{slash}XIN32{slash}EIC{slash}SCOM1PAD0{slash}TC2)") (class "Default")
      (node (ref "C19") (pin "2") (pinfunction "2_2") (pintype "passive"))
      (node (ref "IC5") (pin "1") (pinfunction "PA0/XIN32/EIC/SCOM1PAD0/TC2_1") (pintype "bidirectional"))
      (node (ref "Y1") (pin "P$2") (pinfunction "2_P$2") (pintype "bidirectional"))
    )
    (net (code "34") (name "Net-(IC5-PA1{slash}XOUT32{slash}EIC{slash}SCOM1PAD1{slash}TC2)") (class "Default")
      (node (ref "C20") (pin "2") (pinfunction "2_2") (pintype "passive"))
      (node (ref "IC5") (pin "2") (pinfunction "PA1/XOUT32/EIC/SCOM1PAD1/TC2_2") (pintype "bidirectional"))
      (node (ref "Y1") (pin "P$1") (pinfunction "1_P$1") (pintype "bidirectional"))
    )
    (net (code "35") (name "Net-(IC5-VDDANA)") (class "Default")
      (node (ref "C22") (pin "2") (pinfunction "2_2") (pintype "passive"))
      (node (ref "IC5") (pin "6") (pinfunction "VDDANA_6") (pintype "power_in"))
      (node (ref "L5") (pin "2") (pinfunction "2_2") (pintype "passive"))
    )
    (net (code "36") (name "Net-(IC5-VDDCORE1)") (class "Default")
      (node (ref "C26") (pin "2") (pinfunction "2_2") (pintype "passive"))
      (node (ref "IC5") (pin "43") (pinfunction "VDDCORE1_43") (pintype "input"))
    )
    (net (code "37") (name "Net-(L3-Pad2)") (class "Default")
      (node (ref "L3") (pin "2") (pinfunction "2_2") (pintype "passive"))
      (node (ref "Q4") (pin "3") (pinfunction "D_3") (pintype "passive"))
      (node (ref "Q4") (pin "6") (pinfunction "D_6") (pintype "passive"))
      (node (ref "Q4") (pin "TP1") (pinfunction "D_TP1") (pintype "passive"))
      (node (ref "Q4") (pin "TP2") (pinfunction "D_TP2") (pintype "passive"))
    )
    (net (code "38") (name "Net-(LED1-BLUE)") (class "Default")
      (node (ref "LED1") (pin "3") (pinfunction "BLUE_3") (pintype "passive"))
      (node (ref "R21") (pin "2") (pinfunction "2_2") (pintype "passive"))
    )
    (net (code "39") (name "Net-(LED1-GREEN)") (class "Default")
      (node (ref "LED1") (pin "2") (pinfunction "GREEN_2") (pintype "passive"))
      (node (ref "R20") (pin "2") (pinfunction "2_2") (pintype "passive"))
    )
    (net (code "40") (name "Net-(LED1-RED)") (class "Default")
      (node (ref "LED1") (pin "1") (pinfunction "RED_1") (pintype "passive"))
      (node (ref "R19") (pin "2") (pinfunction "2_2") (pintype "passive"))
    )
    (net (code "41") (name "Net-(LED2-PadK)") (class "Default")
      (node (ref "LED2") (pin "K") (pinfunction "K_K") (pintype "output"))
      (node (ref "R18") (pin "2") (pinfunction "2_2") (pintype "passive"))
    )
    (net (code "42") (name "Net-(LED3-PadK)") (class "Default")
      (node (ref "LED3") (pin "K") (pinfunction "K_K") (pintype "output"))
      (node (ref "R4") (pin "2") (pinfunction "2_2") (pintype "passive"))
    )
    (net (code "43") (name "Net-(Q1-G)") (class "Default")
      (node (ref "Q1") (pin "2") (pinfunction "G_2") (pintype "passive"))
      (node (ref "R39") (pin "2") (pinfunction "2_2") (pintype "passive"))
      (node (ref "R40") (pin "1") (pinfunction "1_1") (pintype "passive"))
    )
    (net (code "44") (name "Net-(Q1-S)") (class "Default")
      (node (ref "Q1") (pin "1") (pinfunction "S_1") (pintype "passive"))
      (node (ref "R12") (pin "2") (pinfunction "2_2") (pintype "passive"))
    )
    (net (code "45") (name "Net-(Q3A-S)") (class "Default")
      (node (ref "C8") (pin "2") (pinfunction "2_2") (pintype "passive"))
      (node (ref "F1") (pin "1") (pinfunction "1_1") (pintype "passive"))
      (node (ref "Q3") (pin "1") (pinfunction "S_1") (pintype "passive"))
      (node (ref "Q3") (pin "4") (pinfunction "S_4") (pintype "passive"))
      (node (ref "R29") (pin "1") (pinfunction "1_1") (pintype "passive"))
    )
    (net (code "46") (name "Net-(TVS1-VBUS)") (class "Default")
      (node (ref "L1") (pin "1") (pinfunction "1_1") (pintype "passive"))
      (node (ref "TVS1") (pin "6") (pinfunction "VBUS_6") (pintype "passive"))
      (node (ref "USB") (pin "P1") (pinfunction "VBUS_P1") (pintype "power_in"))
    )
    (net (code "47") (name "PA30_SWCLK") (class "Default")
      (node (ref "IC5") (pin "45") (pinfunction "PA30/EIC/SCOM1PAD2/TC1_45") (pintype "bidirectional"))
      (node (ref "SWD") (pin "4") (pinfunction "4_4") (pintype "passive"))
    )
    (net (code "48") (name "PA31_SWDIO") (class "Default")
      (node (ref "IC5") (pin "46") (pinfunction "PA31/EIC/SCOM1PAD3/TC1_46") (pintype "bidirectional"))
      (node (ref "SWD") (pin "2") (pinfunction "2_2") (pintype "passive"))
    )
    (net (code "49") (name "PWM_HEATER_CO") (class "Default")
      (node (ref "IC5") (pin "13") (pinfunction "PA8/I2C/AIN16/SCOM2PAD0+/TC0_13") (pintype "bidirectional"))
      (node (ref "JP1") (pin "5") (pinfunction "5_5") (pintype "passive"))
    )
    (net (code "50") (name "PWM_HEATER_NOX") (class "Default")
      (node (ref "IC5") (pin "14") (pinfunction "PA9/I2C/EIC/AIN17/SCOM2PAD1+/TC0_14") (pintype "bidirectional"))
      (node (ref "JP1") (pin "3") (pinfunction "3_3") (pintype "passive"))
    )
    (net (code "51") (name "RESET") (class "Default")
      (node (ref "D1") (pin "+") (pinfunction "+_+") (pintype "passive"))
      (node (ref "IC4") (pin "5") (pinfunction "GPIO14_5") (pintype "bidirectional"))
      (node (ref "P2") (pin "1") (pinfunction "A0_1") (pintype "bidirectional"))
      (node (ref "P2") (pin "2") (pinfunction "A1_2") (pintype "bidirectional"))
      (node (ref "R15") (pin "2") (pinfunction "2_2") (pintype "passive"))
      (node (ref "R16") (pin "1") (pinfunction "1_1") (pintype "passive"))
      (node (ref "SWD") (pin "10") (pinfunction "10_10") (pintype "passive"))
    )
    (net (code "52") (name "RXWIFI") (class "Default")
      (node (ref "IC4") (pin "22") (pinfunction "TXD_22") (pintype "output"))
      (node (ref "IC5") (pin "10") (pinfunction "PA5/EIC/AIN5/SCOM0PAD1/TC0_10") (pintype "bidirectional"))
    )
    (net (code "53") (name "RX_PMS") (class "Default")
      (node (ref "IC5") (pin "48") (pinfunction "PB3/EIC/AIN11/SCOM5PAD1_48") (pintype "bidirectional"))
      (node (ref "JP1") (pin "11") (pinfunction "11_11") (pintype "passive"))
    )
    (net (code "54") (name "SCK") (class "Default")
      (node (ref "IC5") (pin "20") (pinfunction "PB11/EIC/SCOM4PAD3/TC5_20") (pintype "bidirectional"))
      (node (ref "IC6") (pin "6") (pinfunction "SCK_6") (pintype "bidirectional"))
      (node (ref "SD1") (pin "5") (pinfunction "CLK_5") (pintype "bidirectional"))
    )
    (net (code "55") (name "SCL") (class "Default")
      (node (ref "IC1") (pin "A3") (pinfunction "SCL_A3") (pintype "bidirectional"))
      (node (ref "IC2") (pin "5") (pinfunction "SCL_5") (pintype "bidirectional"))
      (node (ref "IC5") (pin "32") (pinfunction "PA23/I2C/EIC/SCOM5PAD1+/TC4_32") (pintype "bidirectional"))
      (node (ref "JP1") (pin "4") (pinfunction "4_4") (pintype "passive"))
      (node (ref "R14") (pin "1") (pinfunction "1_1") (pintype "passive"))
    )
    (net (code "56") (name "SCL_GROOVE") (class "Default")
      (node (ref "IC5") (pin "26") (pinfunction "PA17/I2C/EIC/SCOM1PAD1+/TC2_26") (pintype "bidirectional"))
      (node (ref "R22") (pin "1") (pinfunction "1_1") (pintype "passive"))
      (node (ref "X1") (pin "1") (pinfunction "1_1") (pintype "bidirectional"))
    )
    (net (code "57") (name "SDA") (class "Default")
      (node (ref "IC1") (pin "A2") (pinfunction "SDA_A2") (pintype "bidirectional"))
      (node (ref "IC2") (pin "6") (pinfunction "SDA_6") (pintype "bidirectional"))
      (node (ref "IC5") (pin "31") (pinfunction "PA22/I2C/EIC/SCOM5PAD0+/TC4_31") (pintype "bidirectional"))
      (node (ref "JP1") (pin "6") (pinfunction "6_6") (pintype "passive"))
      (node (ref "R13") (pin "1") (pinfunction "1_1") (pintype "passive"))
    )
    (net (code "58") (name "SDA_GROOVE") (class "Default")
      (node (ref "IC5") (pin "25") (pinfunction "PA16/I2C/EIC/SCOM1PAD0+/TC2_25") (pintype "bidirectional"))
      (node (ref "R23") (pin "1") (pinfunction "1_1") (pintype "passive"))
      (node (ref "X1") (pin "2") (pinfunction "2_2") (pintype "bidirectional"))
    )
    (net (code "59") (name "SW_GROOVE") (class "Default")
      (node (ref "IC5") (pin "38") (pinfunction "PB23/EIC/SCOM5PAD3_38") (pintype "bidirectional"))
      (node (ref "Q3") (pin "2") (pinfunction "G_2") (pintype "passive"))
      (node (ref "Q3") (pin "5") (pinfunction "G_5") (pintype "passive"))
      (node (ref "R29") (pin "2") (pinfunction "2_2") (pintype "passive"))
    )
    (net (code "60") (name "SW_PMS") (class "Default")
      (node (ref "IC5") (pin "41") (pinfunction "PA28/EIC_41") (pintype "bidirectional"))
      (node (ref "JP1") (pin "7") (pinfunction "7_7") (pintype "passive"))
      (node (ref "R27") (pin "2") (pinfunction "2_2") (pintype "passive"))
    )
    (net (code "61") (name "SW_WIFI") (class "Default")
      (node (ref "IC5") (pin "37") (pinfunction "PB22/EIC/SCOM5PAD2_37") (pintype "bidirectional"))
      (node (ref "Q4") (pin "2") (pinfunction "G_2") (pintype "passive"))
      (node (ref "Q4") (pin "5") (pinfunction "G_5") (pintype "passive"))
      (node (ref "R28") (pin "1") (pinfunction "1_1") (pintype "passive"))
    )
    (net (code "62") (name "TARGET_RESET") (class "Default")
      (node (ref "C3") (pin "2") (pinfunction "2_2") (pintype "passive"))
      (node (ref "IC5") (pin "40") (pinfunction "RESETN_40") (pintype "bidirectional"))
      (node (ref "R15") (pin "1") (pinfunction "1_1") (pintype "passive"))
    )
    (net (code "63") (name "TARGET_USB_N") (class "Default")
      (node (ref "IC5") (pin "33") (pinfunction "PA24/EIC/SCOM3PAD2+/TC5_33") (pintype "bidirectional"))
      (node (ref "TVS1") (pin "2") (pinfunction "D-_2") (pintype "passive"))
      (node (ref "USB") (pin "P2") (pinfunction "D-_P2") (pintype "bidirectional"))
    )
    (net (code "64") (name "TARGET_USB_P") (class "Default")
      (node (ref "IC5") (pin "34") (pinfunction "PA25/EIC/SCOM3PAD3+/TC5_34") (pintype "bidirectional"))
      (node (ref "TVS1") (pin "1") (pinfunction "D+_1") (pintype "passive"))
      (node (ref "USB") (pin "P3") (pinfunction "D+_P3") (pintype "bidirectional"))
    )
    (net (code "65") (name "TXLED") (class "Default")
      (node (ref "IC5") (pin "39") (pinfunction "PA27/EIC_39") (pintype "bidirectional"))
      (node (ref "R18") (pin "1") (pinfunction "1_1") (pintype "passive"))
    )
    (net (code "66") (name "TXWIFI") (class "Default")
      (node (ref "IC4") (pin "21") (pinfunction "RXD_21") (pintype "input"))
      (node (ref "IC5") (pin "9") (pinfunction "PA4/EIC/REF/AIN4/SCOM0PAD0/TC0_9") (pintype "bidirectional"))
    )
    (net (code "67") (name "TX_PMS") (class "Default")
      (node (ref "IC5") (pin "47") (pinfunction "PB2/EIC/AIN10/SCOM5PAD0_47") (pintype "bidirectional"))
      (node (ref "JP1") (pin "13") (pinfunction "13_13") (pintype "passive"))
    )
    (net (code "68") (name "USB_ID") (class "Default")
      (node (ref "Q2") (pin "2") (pinfunction "G_2") (pintype "passive"))
      (node (ref "R26") (pin "1") (pinfunction "1_1") (pintype "passive"))
      (node (ref "R7") (pin "2") (pinfunction "2_2") (pintype "passive"))
      (node (ref "TVS1") (pin "3") (pinfunction "ID_3") (pintype "passive"))
      (node (ref "USB") (pin "P4") (pinfunction "ID_P4") (pintype "bidirectional"))
    )
    (net (code "69") (name "VBAT") (class "Default")
      (node (ref "BAT") (pin "2") (pinfunction "2_2") (pintype "passive"))
      (node (ref "C21") (pin "2") (pinfunction "2_2") (pintype "passive"))
      (node (ref "IC1") (pin "C1") (pinfunction "SRP_C1") (pintype "bidirectional"))
      (node (ref "IC1") (pin "C3") (pinfunction "BAT_C3") (pintype "bidirectional"))
      (node (ref "R2") (pin "2") (pinfunction "2_2") (pintype "passive"))
    )
    (net (code "70") (name "VBAT'") (class "Default")
      (node (ref "IC1") (pin "C2") (pinfunction "SRN_C2") (pintype "bidirectional"))
      (node (ref "IC2") (pin "13") (pinfunction "VBAT_13") (pintype "bidirectional"))
      (node (ref "IC2") (pin "14") (pinfunction "VBAT_14") (pintype "bidirectional"))
      (node (ref "JP1") (pin "9") (pinfunction "9_9") (pintype "passive"))
      (node (ref "R2") (pin "1") (pinfunction "1_1") (pintype "passive"))
      (node (ref "R40") (pin "2") (pinfunction "2_2") (pintype "passive"))
    )
    (net (code "71") (name "VCC") (class "Default")
      (node (ref "C2") (pin "2") (pinfunction "2_2") (pintype "passive"))
      (node (ref "C23") (pin "2") (pinfunction "2_2") (pintype "passive"))
      (node (ref "C24") (pin "2") (pinfunction "2_2") (pintype "passive"))
      (node (ref "C25") (pin "2") (pinfunction "2_2") (pintype "passive"))
      (node (ref "C9") (pin "2") (pinfunction "2_2") (pintype "passive"))
      (node (ref "D1") (pin "-") (pinfunction "-_-") (pintype "passive"))
      (node (ref "F1") (pin "2") (pinfunction "2_2") (pintype "passive"))
      (node (ref "F2") (pin "1") (pinfunction "1_1") (pintype "passive"))
      (node (ref "IC5") (pin "17") (pinfunction "VDDIO1_17") (pintype "power_in"))
      (node (ref "IC5") (pin "36") (pinfunction "VDDIO2_36") (pintype "power_in"))
      (node (ref "IC5") (pin "44") (pinfunction "VDDIN_44") (pintype "power_in"))
      (node (ref "IC6") (pin "8") (pinfunction "VCC_8") (pintype "bidirectional"))
      (node (ref "JP1") (pin "1") (pinfunction "1_1") (pintype "passive"))
      (node (ref "JP1") (pin "2") (pinfunction "2_2") (pintype "passive"))
      (node (ref "L5") (pin "1") (pinfunction "1_1") (pintype "passive"))
      (node (ref "LED1") (pin "4") (pinfunction "A_4") (pintype "passive"))
      (node (ref "LED2") (pin "A") (pinfunction "A_A") (pintype "input"))
      (node (ref "LED3") (pin "A") (pinfunction "A_A") (pintype "input"))
      (node (ref "Q4") (pin "1") (pinfunction "S_1") (pintype "passive"))
      (node (ref "Q4") (pin "4") (pinfunction "S_4") (pintype "passive"))
      (node (ref "R13") (pin "2") (pinfunction "2_2") (pintype "passive"))
      (node (ref "R14") (pin "2") (pinfunction "2_2") (pintype "passive"))
      (node (ref "R16") (pin "2") (pinfunction "2_2") (pintype "passive"))
      (node (ref "R17") (pin "2") (pinfunction "2_2") (pintype "passive"))
      (node (ref "R24") (pin "2") (pinfunction "2_2") (pintype "passive"))
      (node (ref "R25") (pin "2") (pinfunction "2_2") (pintype "passive"))
      (node (ref "R26") (pin "2") (pinfunction "2_2") (pintype "passive"))
      (node (ref "R28") (pin "2") (pinfunction "2_2") (pintype "passive"))
      (node (ref "R30") (pin "2") (pinfunction "2_2") (pintype "passive"))
      (node (ref "R38") (pin "2") (pinfunction "2_2") (pintype "passive"))
      (node (ref "R43") (pin "2") (pinfunction "2_2") (pintype "passive"))
      (node (ref "R8") (pin "2") (pinfunction "2_2") (pintype "passive"))
      (node (ref "SD1") (pin "4") (pinfunction "VCC_4") (pintype "bidirectional"))
      (node (ref "SWD") (pin "1") (pinfunction "1_1") (pintype "passive"))
    )
    (net (code "72") (name "VCC_GROOVE") (class "Default")
      (node (ref "Q3") (pin "3") (pinfunction "D_3") (pintype "passive"))
      (node (ref "Q3") (pin "6") (pinfunction "D_6") (pintype "passive"))
      (node (ref "Q3") (pin "TP1") (pinfunction "D_TP1") (pintype "passive"))
      (node (ref "Q3") (pin "TP2") (pinfunction "D_TP2") (pintype "passive"))
      (node (ref "R22") (pin "2") (pinfunction "2_2") (pintype "passive"))
      (node (ref "R23") (pin "2") (pinfunction "2_2") (pintype "passive"))
      (node (ref "X1") (pin "3") (pinfunction "3_3") (pintype "bidirectional"))
    )
    (net (code "73") (name "VCC_WIFI") (class "Default")
      (node (ref "C1") (pin "2") (pinfunction "2_2") (pintype "passive"))
      (node (ref "IC4") (pin "1") (pinfunction "RESET_1") (pintype "input"))
      (node (ref "IC4") (pin "17") (pinfunction "GPIO2_17") (pintype "bidirectional"))
      (node (ref "IC4") (pin "8") (pinfunction "VCC_8") (pintype "power_in"))
      (node (ref "L3") (pin "1") (pinfunction "1_1") (pintype "passive"))
      (node (ref "R3") (pin "2") (pinfunction "2_2") (pintype "passive"))
    )
    (net (code "74") (name "VSYS") (class "Default")
      (node (ref "C10") (pin "2") (pinfunction "2_2") (pintype "passive"))
      (node (ref "C11") (pin "2") (pinfunction "2_2") (pintype "passive"))
      (node (ref "C15") (pin "2") (pinfunction "2_2") (pintype "passive"))
      (node (ref "C16") (pin "2") (pinfunction "2_2") (pintype "passive"))
      (node (ref "IC2") (pin "15") (pinfunction "SYS_15") (pintype "bidirectional"))
      (node (ref "IC2") (pin "16") (pinfunction "SYS_16") (pintype "bidirectional"))
      (node (ref "IC3") (pin "6") (pinfunction "IN_6") (pintype "bidirectional"))
      (node (ref "L2") (pin "2") (pinfunction "2_2") (pintype "bidirectional"))
      (node (ref "R5") (pin "1") (pinfunction "1_1") (pintype "passive"))
    )
    (net (code "75") (name "VUSB") (class "Default")
      (node (ref "C4") (pin "2") (pinfunction "2_2") (pintype "passive"))
      (node (ref "C5") (pin "2") (pinfunction "2_2") (pintype "passive"))
      (node (ref "C6") (pin "2") (pinfunction "2_2") (pintype "passive"))
      (node (ref "IC2") (pin "1") (pinfunction "VBUS_1") (pintype "bidirectional"))
      (node (ref "IC2") (pin "24") (pinfunction "VBUS_24") (pintype "bidirectional"))
      (node (ref "L1") (pin "2") (pinfunction "2_2") (pintype "passive"))
    )
    (net (code "76") (name "WIFI_LED") (class "Default")
      (node (ref "IC4") (pin "19") (pinfunction "GPIO5_19") (pintype "bidirectional"))
      (node (ref "R4") (pin "1") (pinfunction "1_1") (pintype "passive"))
    )
    (net (code "77") (name "unconnected-(IC2-QON-Pad12)") (class "Default")
      (node (ref "IC2") (pin "12") (pinfunction "QON_12") (pintype "bidirectional"))
    )
    (net (code "78") (name "unconnected-(IC2-STAT-Pad4)") (class "Default")
      (node (ref "IC2") (pin "4") (pinfunction "STAT_4") (pintype "bidirectional"))
    )
    (net (code "79") (name "unconnected-(IC2-{slash}PG-Pad3)") (class "Default")
      (node (ref "IC2") (pin "3") (pinfunction "/PG_3") (pintype "bidirectional"))
    )
    (net (code "80") (name "unconnected-(IC3-PG-Pad4)") (class "Default")
      (node (ref "IC3") (pin "4") (pinfunction "PG_4") (pintype "bidirectional"))
    )
    (net (code "81") (name "unconnected-(IC4-ADC-Pad2)") (class "Default")
      (node (ref "IC4") (pin "2") (pinfunction "ADC_2") (pintype "passive"))
    )
    (net (code "82") (name "unconnected-(IC4-GPIO9-Pad11)") (class "Default")
      (node (ref "IC4") (pin "11") (pinfunction "GPIO9_11") (pintype "bidirectional"))
    )
    (net (code "83") (name "unconnected-(IC4-GPIO10-Pad12)") (class "Default")
      (node (ref "IC4") (pin "12") (pinfunction "GPIO10_12") (pintype "bidirectional"))
    )
    (net (code "84") (name "unconnected-(IC4-GPIO12-Pad6)") (class "Default")
      (node (ref "IC4") (pin "6") (pinfunction "GPIO12_6") (pintype "bidirectional"))
    )
    (net (code "85") (name "unconnected-(IC4-GPIO13-Pad7)") (class "Default")
      (node (ref "IC4") (pin "7") (pinfunction "GPIO13_7") (pintype "bidirectional"))
    )
    (net (code "86") (name "unconnected-(IC4-GPIO16-Pad4)") (class "Default")
      (node (ref "IC4") (pin "4") (pinfunction "GPIO16_4") (pintype "bidirectional"))
    )
    (net (code "87") (name "unconnected-(IC4-MISO-Pad10)") (class "Default")
      (node (ref "IC4") (pin "10") (pinfunction "MISO_10") (pintype "passive"))
    )
    (net (code "88") (name "unconnected-(IC4-MOSI-Pad13)") (class "Default")
      (node (ref "IC4") (pin "13") (pinfunction "MOSI_13") (pintype "bidirectional"))
    )
    (net (code "89") (name "unconnected-(IC4-SCLK-Pad14)") (class "Default")
      (node (ref "IC4") (pin "14") (pinfunction "SCLK_14") (pintype "bidirectional"))
    )
    (net (code "90") (name "unconnected-(IC6-IO3{slash}RESET#-Pad7)") (class "Default")
      (node (ref "IC6") (pin "7") (pinfunction "IO3/RESET#_7") (pintype "bidirectional"))
    )
    (net (code "91") (name "unconnected-(IC6-WP#{slash}IO2-Pad3)") (class "Default")
      (node (ref "IC6") (pin "3") (pinfunction "WP#/IO2_3") (pintype "bidirectional"))
    )
    (net (code "92") (name "unconnected-(SD1-DAT1-Pad8)") (class "Default")
      (node (ref "SD1") (pin "8") (pinfunction "DAT1_8") (pintype "bidirectional"))
    )
    (net (code "93") (name "unconnected-(SD1-DAT2-Pad1)") (class "Default")
      (node (ref "SD1") (pin "1") (pinfunction "DAT2_1") (pintype "bidirectional"))
    )
    (net (code "94") (name "unconnected-(SWD-Pad6)") (class "Default")
      (node (ref "SWD") (pin "6") (pinfunction "6_6") (pintype "passive"))
    )
    (net (code "95") (name "unconnected-(SWD-Pad7)") (class "Default")
      (node (ref "SWD") (pin "7") (pinfunction "7_7") (pintype "passive"))
    )
    (net (code "96") (name "unconnected-(SWD-Pad8)") (class "Default")
      (node (ref "SWD") (pin "8") (pinfunction "8_8") (pintype "passive"))
    )
    (net (code "97") (name "unconnected-(TVS1-N.C.-Pad5)") (class "Default")
      (node (ref "TVS1") (pin "5") (pinfunction "N.C._5") (pintype "passive"))
    )
  )
)
